# HHT_CAL-PWR_3_1.net
KiCad netlist of a schematic drawn in Altium Designer
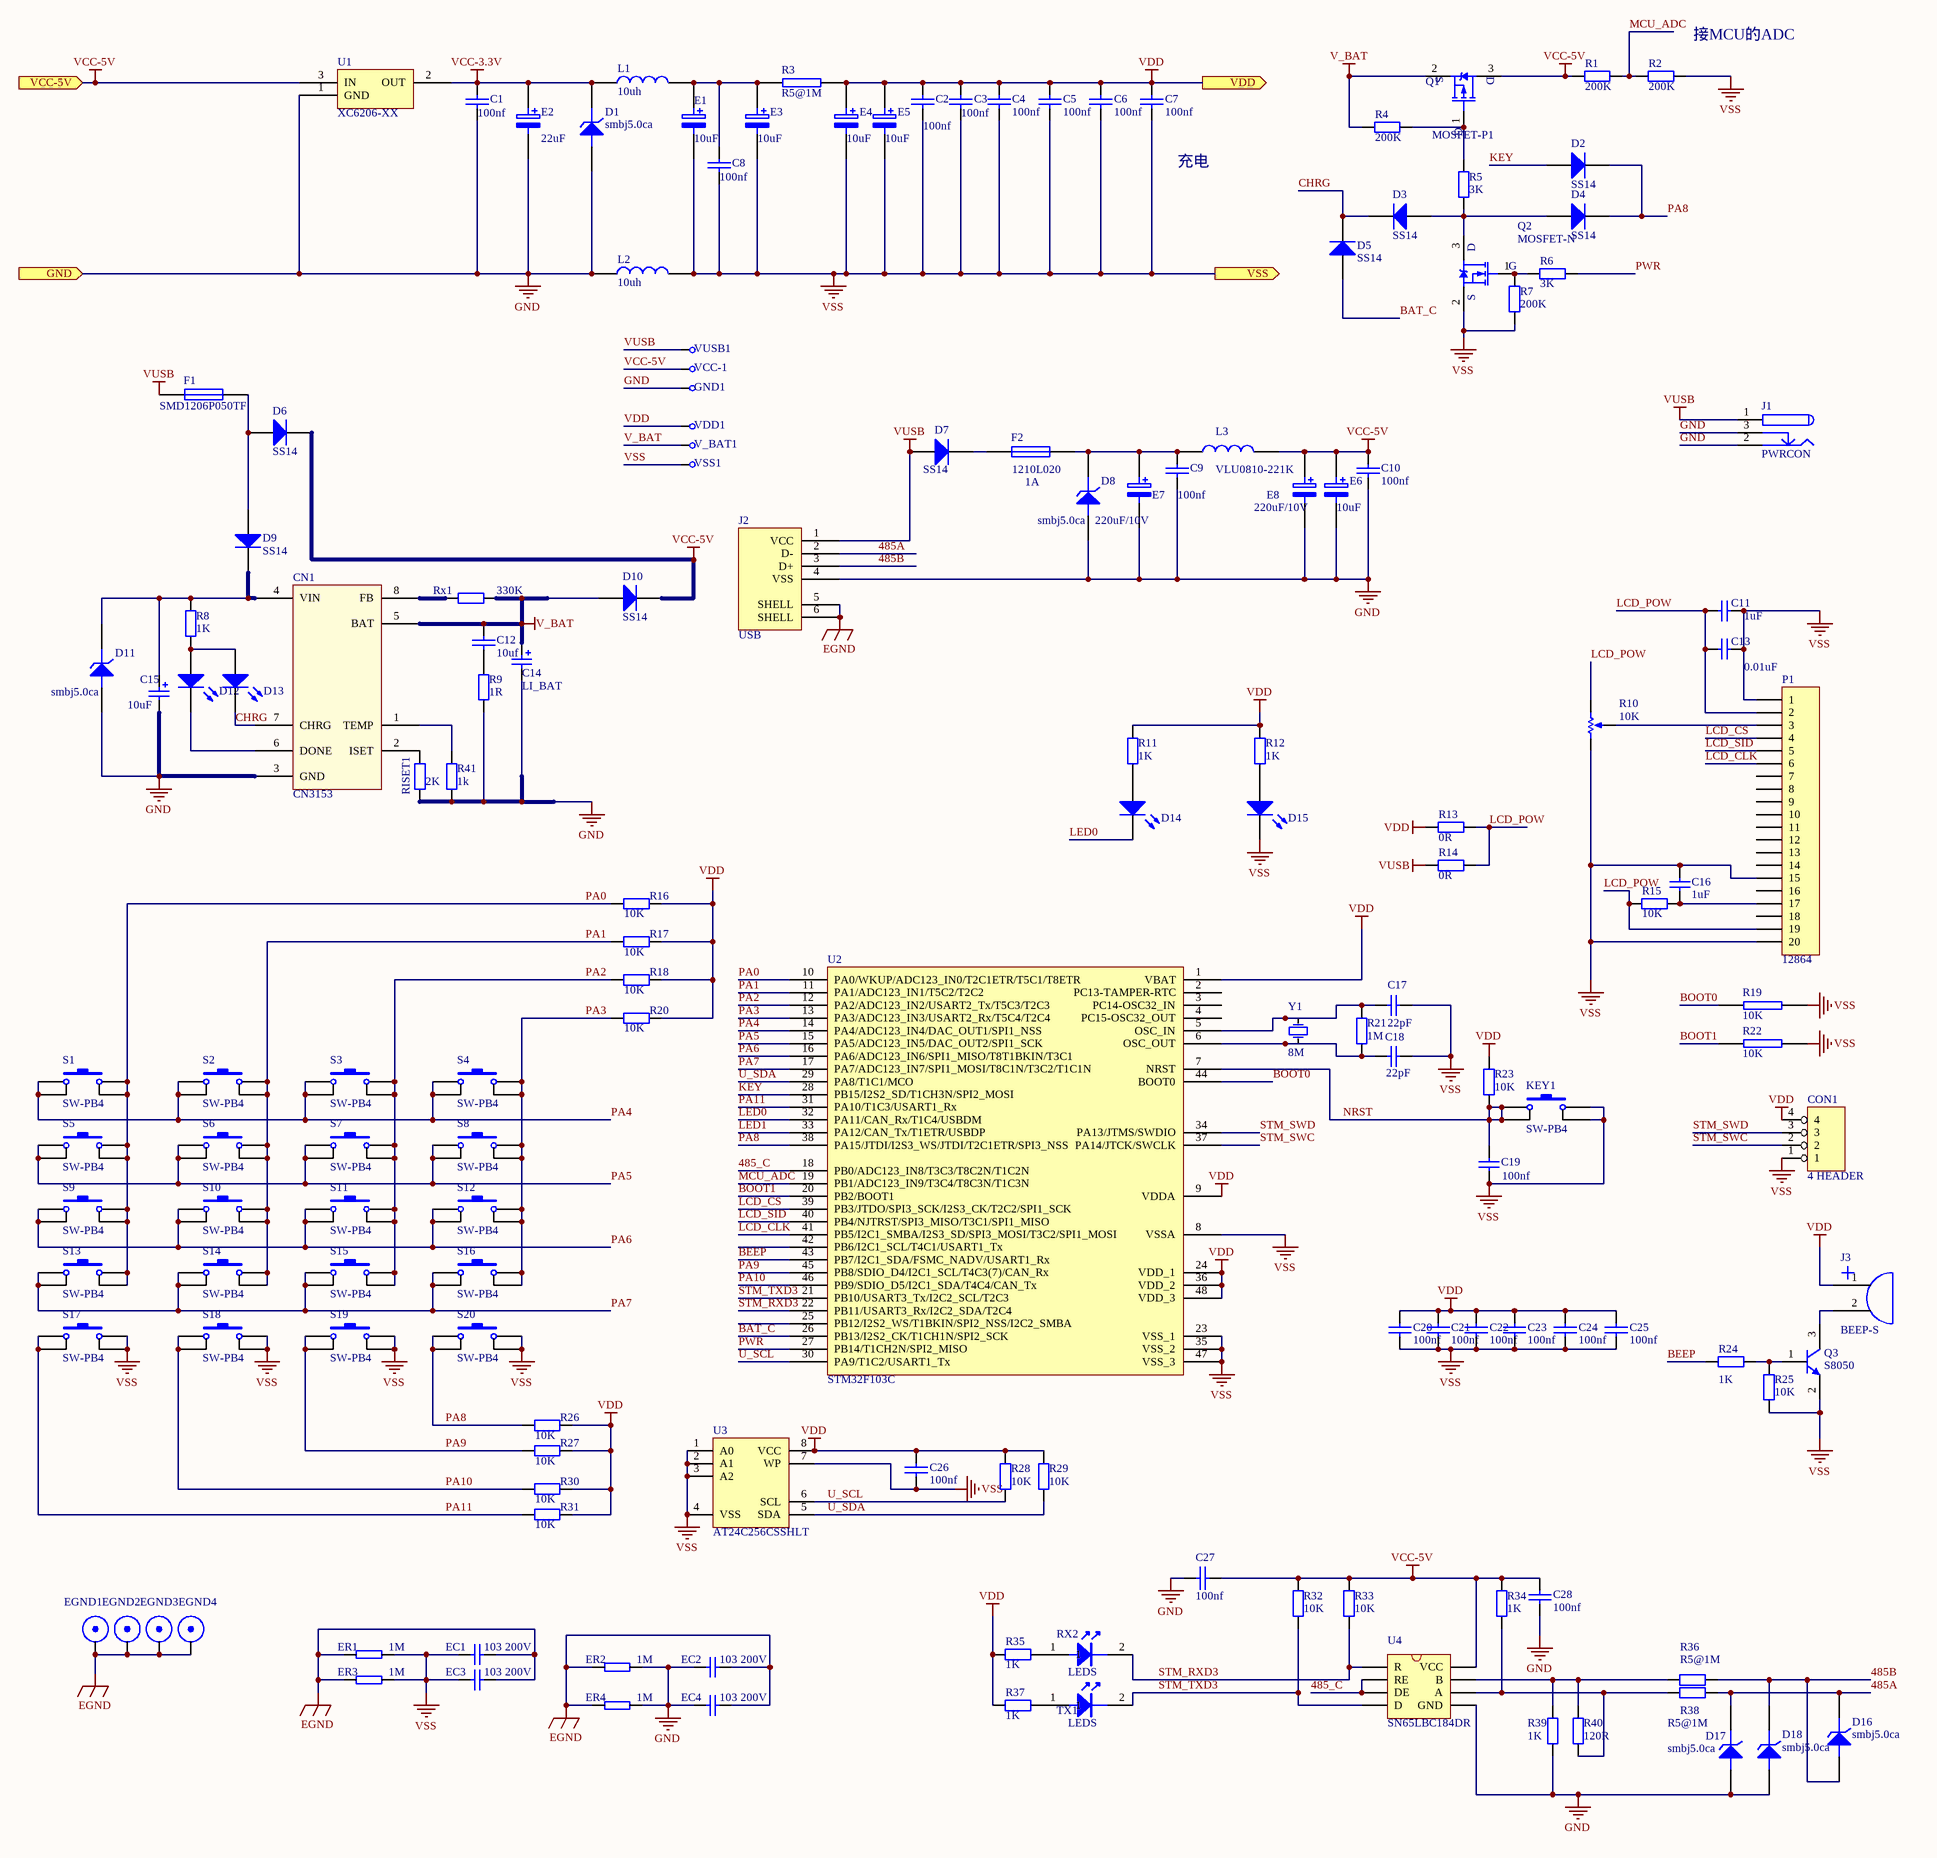
[diagram p0: HHT_CAL-PWR_3.1.SchDoc]

(export (version "E")
  (design (tool "Eeschema 10.0.6"))
  (components
    (comp (ref "C1")
      (value "100nf")
      (footprint "LC-0603_C")
      (description "Capacitor")
      (libsource (lib "Miscellaneous Devices") (part "CAP"))
    )
    (comp (ref "C2")
      (value "100nf")
      (footprint "LC-0603_C")
      (description "Capacitor")
      (libsource (lib "Miscellaneous Devices") (part "CAP"))
    )
    (comp (ref "C3")
      (value "100nf")
      (footprint "LC-0603_C")
      (description "Capacitor")
      (libsource (lib "Miscellaneous Devices") (part "CAP"))
    )
    (comp (ref "C4")
      (value "100nf")
      (footprint "LC-0603_C")
      (description "Capacitor")
      (libsource (lib "Miscellaneous Devices") (part "CAP"))
    )
    (comp (ref "C5")
      (value "100nf")
      (footprint "LC-0603_C")
      (description "Capacitor")
      (libsource (lib "Miscellaneous Devices") (part "CAP"))
    )
    (comp (ref "C6")
      (value "100nf")
      (footprint "LC-0603_C")
      (description "Capacitor")
      (libsource (lib "Miscellaneous Devices") (part "CAP"))
    )
    (comp (ref "C7")
      (value "100nf")
      (footprint "LC-0603_C")
      (description "Capacitor")
      (libsource (lib "Miscellaneous Devices") (part "CAP"))
    )
    (comp (ref "C8")
      (value "100nf")
      (footprint "LC-0603_C")
      (description "Capacitor")
      (libsource (lib "Miscellaneous Devices") (part "CAP"))
    )
    (comp (ref "C9")
      (value "100nf")
      (footprint "LC-0805_C")
      (description "Capacitor")
      (libsource (lib "Miscellaneous Devices") (part "CAP"))
    )
    (comp (ref "C10")
      (value "100nf")
      (footprint "LC-0603_C")
      (description "Capacitor")
      (libsource (lib "Miscellaneous Devices") (part "CAP"))
    )
    (comp (ref "C11")
      (value "1uF")
      (footprint "LC-0603_C")
      (description "贴片瓷片电容")
      (fields (field (name "Comment") "1uf") (field (name "PUBLISHER") "Altium Limited"))
      (libsource (lib "fszhang") (part "Cap-S"))
    )
    (comp (ref "C12")
      (value "10uf")
      (footprint "LC-CASE-A_3216")
      (description "Capacitor")
      (libsource (lib "Miscellaneous Devices") (part "CAP"))
    )
    (comp (ref "C13")
      (value "0.01uF")
      (footprint "LC-0603_C")
      (description "贴片瓷片电容")
      (fields (field (name "PUBLISHER") "Altium Limited"))
      (libsource (lib "fszhang") (part "Cap-S"))
    )
    (comp (ref "C14")
      (value "LI_BAT")
      (footprint "HDR2X1-2.54")
      (description "Polarized Capacitor (Radial)")
      (fields (field (name "PUBLISHER") "Altium Limited"))
      (libsource (lib "Miscellaneous Devices") (part "Cap Pol1"))
    )
    (comp (ref "C15")
      (value "10uF")
      (footprint "LC-CASE-B_3528")
      (description "Polarized Capacitor (Radial)")
      (fields (field (name "Comment") "100uF") (field (name "PUBLISHER") "Altium Limited"))
      (libsource (lib "Miscellaneous Devices") (part "Cap Pol1"))
    )
    (comp (ref "C16")
      (value "1uF")
      (footprint "LC-0603_C")
      (description "贴片瓷片电容")
      (fields (field (name "PUBLISHER") "Altium Limited"))
      (libsource (lib "fszhang") (part "Cap-S"))
    )
    (comp (ref "C17")
      (value "22pF")
      (footprint "LC-0603_C")
      (description "贴片瓷片电容")
      (fields (field (name "Comment") "22PF") (field (name "PUBLISHER") "Altium Limited"))
      (libsource (lib "fszhang") (part "Cap-S"))
    )
    (comp (ref "C18")
      (value "22pF")
      (footprint "LC-0603_C")
      (description "贴片瓷片电容")
      (fields (field (name "Comment") "22PF") (field (name "PUBLISHER") "Altium Limited"))
      (libsource (lib "fszhang") (part "Cap-S"))
    )
    (comp (ref "C19")
      (value "100nf")
      (footprint "LC-0603_C")
      (description "Capacitor")
      (fields (field (name "PUBLISHER") "Altium Limited"))
      (libsource (lib "Miscellaneous Devices") (part "Cap"))
    )
    (comp (ref "C20")
      (value "100nf")
      (footprint "LC-0603_C")
      (description "Capacitor")
      (libsource (lib "Miscellaneous Devices") (part "CAP"))
    )
    (comp (ref "C21")
      (value "100nf")
      (footprint "LC-0603_C")
      (description "Capacitor")
      (libsource (lib "Miscellaneous Devices") (part "CAP"))
    )
    (comp (ref "C22")
      (value "100nf")
      (footprint "LC-0603_C")
      (description "Capacitor")
      (libsource (lib "Miscellaneous Devices") (part "CAP"))
    )
    (comp (ref "C23")
      (value "100nf")
      (footprint "LC-0603_C")
      (description "Capacitor")
      (libsource (lib "Miscellaneous Devices") (part "CAP"))
    )
    (comp (ref "C24")
      (value "100nf")
      (footprint "LC-0603_C")
      (description "Capacitor")
      (libsource (lib "Miscellaneous Devices") (part "CAP"))
    )
    (comp (ref "C25")
      (value "100nf")
      (footprint "LC-0603_C")
      (description "Capacitor")
      (libsource (lib "Miscellaneous Devices") (part "CAP"))
    )
    (comp (ref "C26")
      (value "100nf")
      (footprint "LC-0603_C")
      (description "Capacitor")
      (libsource (lib "Miscellaneous Devices") (part "CAP"))
    )
    (comp (ref "C27")
      (value "100nf")
      (footprint "LC-0603_C")
      (description "Capacitor")
      (libsource (lib "Miscellaneous Devices") (part "CAP"))
    )
    (comp (ref "C28")
      (value "100nf")
      (footprint "LC-0603_C")
      (description "Capacitor")
      (libsource (lib "Miscellaneous Devices") (part "CAP"))
    )
    (comp (ref "CN1") (value "CN3153") (footprint "SOIC8") (libsource (lib "PCB_Project1") (part "CN3153")))
    (comp (ref "CON1")
      (value "4 HEADER")
      (footprint "sip4")
      (description "4 Pin Header")
      (libsource (lib "Miscellaneous Devices") (part "4 HEADER"))
    )
    (comp (ref "D1")
      (value "smbj5.0ca")
      (footprint "LC-SMB(DO-214AA)_S1")
      (description "Zener Diode")
      (libsource (lib "Miscellaneous Devices") (part "ZENER3"))
    )
    (comp (ref "D2")
      (value "SS14")
      (footprint "LC-SMA(DO-214AC)_S5")
      (description "Default Diode")
      (fields (field (name "PUBLISHER") "Altium Limited"))
      (libsource (lib "Miscellaneous Devices") (part "Diode"))
    )
    (comp (ref "D3")
      (value "SS14")
      (footprint "LC-SMA(DO-214AC)_S5")
      (description "Default Diode")
      (fields (field (name "PUBLISHER") "Altium Limited"))
      (libsource (lib "Miscellaneous Devices") (part "Diode"))
    )
    (comp (ref "D4")
      (value "SS14")
      (footprint "LC-SMA(DO-214AC)_S5")
      (description "Default Diode")
      (fields (field (name "PUBLISHER") "Altium Limited"))
      (libsource (lib "Miscellaneous Devices") (part "Diode"))
    )
    (comp (ref "D5")
      (value "SS14")
      (footprint "LC-SMA(DO-214AC)_S5")
      (description "Default Diode")
      (fields (field (name "PUBLISHER") "Altium Limited"))
      (libsource (lib "Miscellaneous Devices") (part "Diode"))
    )
    (comp (ref "D6")
      (value "SS14")
      (footprint "LC-SMA(DO-214AC)_S5")
      (description "Default Diode")
      (fields (field (name "PUBLISHER") "Altium Limited"))
      (libsource (lib "Miscellaneous Devices") (part "Diode"))
    )
    (comp (ref "D7")
      (value "SS14")
      (footprint "LC-SMA(DO-214AC)_S5")
      (description "整流二极管")
      (fields (field (name "PUBLISHER") "Altium Limited"))
      (libsource (lib "fszhang") (part "Diode-R"))
    )
    (comp (ref "D8")
      (value "smbj5.0ca")
      (footprint "LC-SMB(DO-214AA)_S1")
      (description "Zener Diode")
      (libsource (lib "Miscellaneous Devices") (part "ZENER3"))
    )
    (comp (ref "D9")
      (value "SS14")
      (footprint "LC-SMA(DO-214AC)_S5")
      (description "Default Diode")
      (fields (field (name "PUBLISHER") "Altium Limited"))
      (libsource (lib "Miscellaneous Devices") (part "Diode"))
    )
    (comp (ref "D10")
      (value "SS14")
      (footprint "LC-SMA(DO-214AC)_S5")
      (description "Default Diode")
      (fields (field (name "PUBLISHER") "Altium Limited"))
      (libsource (lib "Miscellaneous Devices") (part "Diode"))
    )
    (comp (ref "D11")
      (value "smbj5.0ca")
      (footprint "LC-SMA(DO-214AC)_S5")
      (description "Zener Diode")
      (libsource (lib "Miscellaneous Devices") (part "ZENER3"))
    )
    (comp (ref "D12")
      (value "LED0")
      (footprint "LED-0805")
      (description "发光二极管")
      (fields (field (name "PUBLISHER") "Altium Limited"))
      (libsource (lib "fszhang") (part "LED0"))
    )
    (comp (ref "D13")
      (value "LED0")
      (footprint "LED-0805")
      (description "发光二极管")
      (fields (field (name "PUBLISHER") "Altium Limited"))
      (libsource (lib "fszhang") (part "LED0"))
    )
    (comp (ref "D14")
      (value "LED0")
      (footprint "LC-0805_LED_S1")
      (description "发光二极管")
      (fields (field (name "PUBLISHER") "Altium Limited"))
      (libsource (lib "fszhang") (part "LED0"))
    )
    (comp (ref "D15")
      (value "LED0")
      (footprint "LC-0805_LED_S1")
      (description "发光二极管")
      (fields (field (name "PUBLISHER") "Altium Limited"))
      (libsource (lib "fszhang") (part "LED0"))
    )
    (comp (ref "D16")
      (value "smbj5.0ca")
      (footprint "LC-SMB(DO-214AA)_S1")
      (description "Zener Diode")
      (libsource (lib "Miscellaneous Devices") (part "ZENER3"))
    )
    (comp (ref "D17")
      (value "smbj5.0ca")
      (footprint "LC-SMB(DO-214AA)_S1")
      (description "Zener Diode")
      (libsource (lib "Miscellaneous Devices") (part "ZENER3"))
    )
    (comp (ref "D18")
      (value "smbj5.0ca")
      (footprint "LC-SMB(DO-214AA)_S1")
      (description "Zener Diode")
      (libsource (lib "Miscellaneous Devices") (part "ZENER3"))
    )
    (comp (ref "E1")
      (value "10uF")
      (footprint "LC-CASE-A_3216")
      (description "Electrolytic Capacitor")
      (libsource (lib "Miscellaneous Devices") (part "ELECTRO2"))
    )
    (comp (ref "E2")
      (value "22uF")
      (footprint "HONOR_63X54")
      (description "Electrolytic Capacitor")
      (libsource (lib "Miscellaneous Devices") (part "ELECTRO2"))
    )
    (comp (ref "E3")
      (value "10uF")
      (footprint "LC-CASE-A_3216")
      (description "Electrolytic Capacitor")
      (libsource (lib "Miscellaneous Devices") (part "ELECTRO2"))
    )
    (comp (ref "E4")
      (value "10uF")
      (footprint "LC-CASE-A_3216")
      (description "Electrolytic Capacitor")
      (libsource (lib "Miscellaneous Devices") (part "ELECTRO2"))
    )
    (comp (ref "E5")
      (value "10uF")
      (footprint "LC-CASE-A_3216")
      (description "Electrolytic Capacitor")
      (libsource (lib "Miscellaneous Devices") (part "ELECTRO2"))
    )
    (comp (ref "E6")
      (value "10uF")
      (footprint "LC-CASE-B_3528")
      (description "Electrolytic Capacitor")
      (libsource (lib "Miscellaneous Devices") (part "ELECTRO2"))
    )
    (comp (ref "E7")
      (value "220uF/10V")
      (footprint "HONOR_63X54")
      (description "Electrolytic Capacitor")
      (libsource (lib "Miscellaneous Devices") (part "ELECTRO2"))
    )
    (comp (ref "E8")
      (value "220uF/10V")
      (footprint "HONOR_63X54")
      (description "Electrolytic Capacitor")
      (libsource (lib "Miscellaneous Devices") (part "ELECTRO2"))
    )
    (comp (ref "EC1")
      (value "103 200V")
      (footprint "LC-1206_C")
      (description "Capacitor")
      (fields (field (name "PUBLISHER") "Altium Limited"))
      (libsource (lib "Miscellaneous Devices") (part "Cap"))
    )
    (comp (ref "EC2")
      (value "103 200V")
      (footprint "LC-1206_C")
      (description "Capacitor")
      (fields (field (name "PUBLISHER") "Altium Limited"))
      (libsource (lib "Miscellaneous Devices") (part "Cap"))
    )
    (comp (ref "EC3")
      (value "103 200V")
      (footprint "LC-1206_C")
      (description "Capacitor")
      (fields (field (name "PUBLISHER") "Altium Limited"))
      (libsource (lib "Miscellaneous Devices") (part "Cap"))
    )
    (comp (ref "EC4")
      (value "103 200V")
      (footprint "LC-1206_C")
      (description "Capacitor")
      (fields (field (name "PUBLISHER") "Altium Limited"))
      (libsource (lib "Miscellaneous Devices") (part "Cap"))
    )
    (comp (ref "EGND1")
      (value "EGND")
      (footprint "H-6-3.2m")
      (libsource (lib "PCB_Project_11") (part "EGND"))
    )
    (comp (ref "EGND2")
      (value "EGND")
      (footprint "H-6-3.2m")
      (libsource (lib "PCB_Project_11") (part "EGND"))
    )
    (comp (ref "EGND3")
      (value "EGND")
      (footprint "H-6-3.2m")
      (libsource (lib "PCB_Project_11") (part "EGND"))
    )
    (comp (ref "EGND4")
      (value "EGND")
      (footprint "H-6-3.2m")
      (libsource (lib "PCB_Project_11") (part "EGND"))
    )
    (comp (ref "ER1") (value "1M") (footprint "LC-1206_R") (libsource (lib "*") (part "RES2")))
    (comp (ref "ER2") (value "1M") (footprint "LC-1206_R") (libsource (lib "*") (part "RES2")))
    (comp (ref "ER3") (value "1M") (footprint "LC-1206_R") (libsource (lib "*") (part "RES2")))
    (comp (ref "ER4") (value "1M") (footprint "LC-1206_R") (libsource (lib "*") (part "RES2")))
    (comp (ref "F1")
      (value "SMD1206P050TF")
      (footprint "LC-1206_R")
      (description "Fuse")
      (fields (field (name "PUBLISHER") "Altium Limited"))
      (libsource (lib "Miscellaneous Devices") (part "Fuse 1"))
    )
    (comp (ref "F2")
      (value "1210L020")
      (footprint "LC-0805_R")
      (description "保险丝")
      (fields (field (name "ALTIUM_VALUE") "1A"))
      (libsource (lib "SCH_Footp1_Lian") (part "Fuse1"))
    )
    (comp (ref "GND1")
      (value "CHECK")
      (footprint "CHECK-B")
      (description "测试点")
      (libsource (lib "fszhang") (part "CHECK"))
    )
    (comp (ref "J1")
      (value "PWRCON")
      (footprint "DC-005")
      (description "直流电源端子")
      (fields (field (name "PUBLISHER") "Altium Limited"))
      (libsource (lib "HDR_fszhang") (part "PWRCON"))
    )
    (comp (ref "J2")
      (value "USB")
      (footprint "USB-4-A")
      (description "USB接口")
      (libsource (lib "HDR_fszhang") (part "USB"))
    )
    (comp (ref "J3")
      (value "BEEP-S")
      (footprint "BEEP-S")
      (description "有源蜂鸣器")
      (libsource (lib "fszhang") (part "BEEP-S"))
    )
    (comp (ref "KEY1")
      (value "SW-PB4")
      (footprint "金属轻触开关")
      (description "微动开关")
      (fields (field (name "PUBLISHER") "Altium Limited"))
      (libsource (lib "fszhang") (part "SW-PB4"))
    )
    (comp (ref "L1")
      (value "10uh")
      (footprint "LC-0805_L")
      (libsource (lib "Miscellaneous Devices") (part "INDUCTOR"))
    )
    (comp (ref "L2")
      (value "10uh")
      (footprint "LC-0805_L")
      (libsource (lib "Miscellaneous Devices") (part "INDUCTOR"))
    )
    (comp (ref "L3")
      (value "VLU0810-221K")
      (footprint "L-SMD-7")
      (libsource (lib "Miscellaneous Devices") (part "INDUCTOR"))
    )
    (comp (ref "P1")
      (value "12864")
      (footprint "HDR1X20")
      (description "Header, 20-Pin")
      (fields (field (name "PUBLISHER") "Altium Limited"))
      (libsource (lib "Miscellaneous Connectors") (part "Header 20"))
    )
    (comp (ref "Q1") (value "MOSFET-P1") (footprint "SOT23-3") (libsource (lib "fszhang") (part "MOSFET-P1")))
    (comp (ref "Q2")
      (value "MOSFET-N")
      (footprint "LC-SOT-23(SOT-23-3)")
      (description "N-Channel MOSFET")
      (fields (field (name "PUBLISHER") "Altium Limited"))
      (libsource (lib "fszhang") (part "MOSFET-N"))
    )
    (comp (ref "Q3")
      (value "S8050")
      (footprint "SOT23-3")
      (description "贴片三极管")
      (fields (field (name "PUBLISHER") "Altium Limited"))
      (libsource (lib "fszhang") (part "NPN1"))
    )
    (comp (ref "R1")
      (value "200K")
      (footprint "LC-0603_R")
      (description "Resistor")
      (fields (field (name "PUBLISHER") "Altium Limited"))
      (libsource (lib "Miscellaneous Devices") (part "Res2"))
    )
    (comp (ref "R2")
      (value "200K")
      (footprint "LC-0603_R")
      (description "Resistor")
      (fields (field (name "PUBLISHER") "Altium Limited"))
      (libsource (lib "Miscellaneous Devices") (part "Res2"))
    )
    (comp (ref "R3")
      (value "R5@1M")
      (footprint "LC-0805_R")
      (libsource (lib "Miscellaneous Devices") (part "RES2"))
    )
    (comp (ref "R4")
      (value "200K")
      (footprint "LC-0603_R")
      (description "Resistor")
      (fields (field (name "PUBLISHER") "Altium Limited"))
      (libsource (lib "Miscellaneous Devices") (part "Res2"))
    )
    (comp (ref "R5")
      (value "3K")
      (footprint "LC-0603_R")
      (description "Resistor")
      (fields (field (name "PUBLISHER") "Altium Limited"))
      (libsource (lib "") (part "Res2_1"))
    )
    (comp (ref "R6")
      (value "3K")
      (footprint "LC-0603_R")
      (description "Resistor")
      (fields (field (name "PUBLISHER") "Altium Limited"))
      (libsource (lib "") (part "Res2_3"))
    )
    (comp (ref "R7")
      (value "200K")
      (footprint "LC-0603_R")
      (description "Resistor")
      (fields (field (name "PUBLISHER") "Altium Limited"))
      (libsource (lib "") (part "Res2_1"))
    )
    (comp (ref "R8")
      (value "1K")
      (footprint "LC-0603_R")
      (description "Resistor")
      (fields (field (name "PUBLISHER") "Altium Limited"))
      (libsource (lib "") (part "Res2_1"))
    )
    (comp (ref "R9")
      (value "1R")
      (footprint "LC-0603_R")
      (description "Resistor")
      (fields (field (name "PUBLISHER") "Altium Limited"))
      (libsource (lib "") (part "Res2_2"))
    )
    (comp (ref "R10")
      (value "10K")
      (footprint "VR-3296W")
      (description "精密可调电阻")
      (fields (field (name "Comment") "RPot") (field (name "PUBLISHER") "Altium Limited"))
      (libsource (lib "fszhang") (part "RPot"))
    )
    (comp (ref "R11")
      (value "1K")
      (footprint "0805-1")
      (description "贴片电阻")
      (fields (field (name "PUBLISHER") "Altium Limited"))
      (libsource (lib "fszhang") (part "Res1"))
    )
    (comp (ref "R12")
      (value "1K")
      (footprint "0805-1")
      (description "贴片电阻")
      (fields (field (name "PUBLISHER") "Altium Limited"))
      (libsource (lib "fszhang") (part "Res1"))
    )
    (comp (ref "R13")
      (value "0R")
      (footprint "LC-0805_R")
      (description "贴片电阻")
      (fields (field (name "PUBLISHER") "Altium Limited"))
      (libsource (lib "") (part "Res1_1"))
    )
    (comp (ref "R14")
      (value "0R")
      (footprint "LC-0805_R")
      (description "贴片电阻")
      (fields (field (name "PUBLISHER") "Altium Limited"))
      (libsource (lib "") (part "Res1_1"))
    )
    (comp (ref "R15")
      (value "10K")
      (footprint "0805-1")
      (description "贴片电阻")
      (fields (field (name "PUBLISHER") "Altium Limited"))
      (libsource (lib "") (part "Res1_1"))
    )
    (comp (ref "R16")
      (value "10K")
      (footprint "LC-0603_R")
      (description "贴片电阻")
      (fields (field (name "PUBLISHER") "Altium Limited"))
      (libsource (lib "") (part "Res1_1"))
    )
    (comp (ref "R17")
      (value "10K")
      (footprint "LC-0603_R")
      (description "贴片电阻")
      (fields (field (name "PUBLISHER") "Altium Limited"))
      (libsource (lib "") (part "Res1_1"))
    )
    (comp (ref "R18")
      (value "10K")
      (footprint "LC-0603_R")
      (description "贴片电阻")
      (fields (field (name "PUBLISHER") "Altium Limited"))
      (libsource (lib "") (part "Res1_1"))
    )
    (comp (ref "R19")
      (value "10K")
      (footprint "LC-0603_R")
      (libsource (lib "Miscellaneous Devices") (part "RES2"))
    )
    (comp (ref "R20")
      (value "10K")
      (footprint "LC-0603_R")
      (description "贴片电阻")
      (fields (field (name "PUBLISHER") "Altium Limited"))
      (libsource (lib "") (part "Res1_1"))
    )
    (comp (ref "R21")
      (value "1M")
      (footprint "0603-1")
      (description "贴片电阻")
      (fields (field (name "PUBLISHER") "Altium Limited"))
      (libsource (lib "fszhang") (part "Res1"))
    )
    (comp (ref "R22")
      (value "10K")
      (footprint "LC-0603_R")
      (libsource (lib "Miscellaneous Devices") (part "RES2"))
    )
    (comp (ref "R23")
      (value "10K")
      (footprint "LC-0603_R")
      (description "Resistor")
      (fields (field (name "PUBLISHER") "Altium Limited"))
      (libsource (lib "") (part "Res2_1"))
    )
    (comp (ref "R24")
      (value "1K")
      (footprint "LC-0603_R")
      (description "贴片电阻")
      (fields (field (name "PUBLISHER") "Altium Limited"))
      (libsource (lib "") (part "Res1_1"))
    )
    (comp (ref "R25")
      (value "10K")
      (footprint "LC-0603_R")
      (description "贴片电阻")
      (fields (field (name "Comment") "10k") (field (name "PUBLISHER") "Altium Limited"))
      (libsource (lib "fszhang") (part "Res1"))
    )
    (comp (ref "R26")
      (value "10K")
      (footprint "LC-0603_R")
      (description "贴片电阻")
      (fields (field (name "PUBLISHER") "Altium Limited"))
      (libsource (lib "") (part "Res1_1"))
    )
    (comp (ref "R27")
      (value "10K")
      (footprint "LC-0603_R")
      (description "贴片电阻")
      (fields (field (name "PUBLISHER") "Altium Limited"))
      (libsource (lib "") (part "Res1_1"))
    )
    (comp (ref "R28")
      (value "10K")
      (footprint "LC-0603_R")
      (description "Resistor")
      (fields (field (name "PUBLISHER") "Altium Limited"))
      (libsource (lib "") (part "Res2_2"))
    )
    (comp (ref "R29")
      (value "10K")
      (footprint "LC-0603_R")
      (description "Resistor")
      (fields (field (name "PUBLISHER") "Altium Limited"))
      (libsource (lib "") (part "Res2_2"))
    )
    (comp (ref "R30")
      (value "10K")
      (footprint "LC-0603_R")
      (description "贴片电阻")
      (fields (field (name "PUBLISHER") "Altium Limited"))
      (libsource (lib "") (part "Res1_1"))
    )
    (comp (ref "R31")
      (value "10K")
      (footprint "LC-0603_R")
      (description "贴片电阻")
      (fields (field (name "PUBLISHER") "Altium Limited"))
      (libsource (lib "") (part "Res1_1"))
    )
    (comp (ref "R32")
      (value "10K")
      (footprint "LC-0603_r")
      (description "Resistor")
      (fields (field (name "PUBLISHER") "Altium Limited"))
      (libsource (lib "") (part "Res2_1"))
    )
    (comp (ref "R33")
      (value "10K")
      (footprint "LC-0603_r")
      (description "Resistor")
      (fields (field (name "PUBLISHER") "Altium Limited"))
      (libsource (lib "") (part "Res2_1"))
    )
    (comp (ref "R34")
      (value "1K")
      (footprint "LC-0603_R")
      (description "Resistor")
      (fields (field (name "PUBLISHER") "Altium Limited"))
      (libsource (lib "") (part "Res2_1"))
    )
    (comp (ref "R35")
      (value "1K")
      (footprint "LC-0603_R")
      (description "Resistor")
      (fields (field (name "PUBLISHER") "Altium Limited"))
      (libsource (lib "Miscellaneous Devices") (part "Res2"))
    )
    (comp (ref "R36")
      (value "R5@1M")
      (footprint "LC-0805_R")
      (description "Resistor")
      (fields (field (name "PUBLISHER") "Altium Limited"))
      (libsource (lib "") (part "Res2_3"))
    )
    (comp (ref "R37")
      (value "1K")
      (footprint "LC-0603_R")
      (description "Resistor")
      (fields (field (name "PUBLISHER") "Altium Limited"))
      (libsource (lib "Miscellaneous Devices") (part "Res2"))
    )
    (comp (ref "R38")
      (value "R5@1M")
      (footprint "LC-0805_R")
      (description "Resistor")
      (fields (field (name "PUBLISHER") "Altium Limited"))
      (libsource (lib "") (part "Res2_3"))
    )
    (comp (ref "R39")
      (value "1K")
      (footprint "LC-0603_R")
      (description "Resistor")
      (fields (field (name "PUBLISHER") "Altium Limited"))
      (libsource (lib "") (part "Res2_1"))
    )
    (comp (ref "R40")
      (value "120R")
      (footprint "LC-0603_R")
      (description "Resistor")
      (fields (field (name "PUBLISHER") "Altium Limited"))
      (libsource (lib "") (part "Res2_1"))
    )
    (comp (ref "R41")
      (value "1k")
      (footprint "LC-0603_R")
      (description "Resistor")
      (fields (field (name "PUBLISHER") "Altium Limited"))
      (libsource (lib "") (part "Res2_2"))
    )
    (comp (ref "RISET1")
      (value "2K")
      (footprint "LC-0603_R")
      (description "Resistor")
      (fields (field (name "PUBLISHER") "Altium Limited"))
      (libsource (lib "") (part "Res2_2"))
    )
    (comp (ref "Rx1")
      (value "330K")
      (footprint "LC-0603_R")
      (description "Resistor")
      (fields (field (name "PUBLISHER") "Altium Limited"))
      (libsource (lib "") (part "Res2_3"))
    )
    (comp (ref "RX2")
      (value "LEDS")
      (footprint "LC-0805_LED_S1")
      (libsource (lib "SCH_Footp1_Lian") (part "LEDS"))
    )
    (comp (ref "S1")
      (value "SW-PB4")
      (footprint "金属轻触开关")
      (description "微动开关")
      (fields (field (name "PUBLISHER") "Altium Limited"))
      (libsource (lib "fszhang") (part "SW-PB4"))
    )
    (comp (ref "S2")
      (value "SW-PB4")
      (footprint "金属轻触开关")
      (description "微动开关")
      (fields (field (name "PUBLISHER") "Altium Limited"))
      (libsource (lib "fszhang") (part "SW-PB4"))
    )
    (comp (ref "S3")
      (value "SW-PB4")
      (footprint "金属轻触开关")
      (description "微动开关")
      (fields (field (name "PUBLISHER") "Altium Limited"))
      (libsource (lib "fszhang") (part "SW-PB4"))
    )
    (comp (ref "S4")
      (value "SW-PB4")
      (footprint "金属轻触开关")
      (description "微动开关")
      (fields (field (name "PUBLISHER") "Altium Limited"))
      (libsource (lib "fszhang") (part "SW-PB4"))
    )
    (comp (ref "S5")
      (value "SW-PB4")
      (footprint "金属轻触开关")
      (description "微动开关")
      (fields (field (name "PUBLISHER") "Altium Limited"))
      (libsource (lib "fszhang") (part "SW-PB4"))
    )
    (comp (ref "S6")
      (value "SW-PB4")
      (footprint "金属轻触开关")
      (description "微动开关")
      (fields (field (name "PUBLISHER") "Altium Limited"))
      (libsource (lib "fszhang") (part "SW-PB4"))
    )
    (comp (ref "S7")
      (value "SW-PB4")
      (footprint "金属轻触开关")
      (description "微动开关")
      (fields (field (name "PUBLISHER") "Altium Limited"))
      (libsource (lib "fszhang") (part "SW-PB4"))
    )
    (comp (ref "S8")
      (value "SW-PB4")
      (footprint "金属轻触开关")
      (description "微动开关")
      (fields (field (name "PUBLISHER") "Altium Limited"))
      (libsource (lib "fszhang") (part "SW-PB4"))
    )
    (comp (ref "S9")
      (value "SW-PB4")
      (footprint "金属轻触开关")
      (description "微动开关")
      (fields (field (name "PUBLISHER") "Altium Limited"))
      (libsource (lib "fszhang") (part "SW-PB4"))
    )
    (comp (ref "S10")
      (value "SW-PB4")
      (footprint "金属轻触开关")
      (description "微动开关")
      (fields (field (name "PUBLISHER") "Altium Limited"))
      (libsource (lib "fszhang") (part "SW-PB4"))
    )
    (comp (ref "S11")
      (value "SW-PB4")
      (footprint "金属轻触开关")
      (description "微动开关")
      (fields (field (name "PUBLISHER") "Altium Limited"))
      (libsource (lib "fszhang") (part "SW-PB4"))
    )
    (comp (ref "S12")
      (value "SW-PB4")
      (footprint "金属轻触开关")
      (description "微动开关")
      (fields (field (name "PUBLISHER") "Altium Limited"))
      (libsource (lib "fszhang") (part "SW-PB4"))
    )
    (comp (ref "S13")
      (value "SW-PB4")
      (footprint "金属轻触开关")
      (description "微动开关")
      (fields (field (name "PUBLISHER") "Altium Limited"))
      (libsource (lib "fszhang") (part "SW-PB4"))
    )
    (comp (ref "S14")
      (value "SW-PB4")
      (footprint "金属轻触开关")
      (description "微动开关")
      (fields (field (name "PUBLISHER") "Altium Limited"))
      (libsource (lib "fszhang") (part "SW-PB4"))
    )
    (comp (ref "S15")
      (value "SW-PB4")
      (footprint "金属轻触开关")
      (description "微动开关")
      (fields (field (name "PUBLISHER") "Altium Limited"))
      (libsource (lib "fszhang") (part "SW-PB4"))
    )
    (comp (ref "S16")
      (value "SW-PB4")
      (footprint "金属轻触开关")
      (description "微动开关")
      (fields (field (name "PUBLISHER") "Altium Limited"))
      (libsource (lib "fszhang") (part "SW-PB4"))
    )
    (comp (ref "S17")
      (value "SW-PB4")
      (footprint "金属轻触开关")
      (description "微动开关")
      (fields (field (name "PUBLISHER") "Altium Limited"))
      (libsource (lib "fszhang") (part "SW-PB4"))
    )
    (comp (ref "S18")
      (value "SW-PB4")
      (footprint "金属轻触开关")
      (description "微动开关")
      (fields (field (name "PUBLISHER") "Altium Limited"))
      (libsource (lib "fszhang") (part "SW-PB4"))
    )
    (comp (ref "S19")
      (value "SW-PB4")
      (footprint "金属轻触开关")
      (description "微动开关")
      (fields (field (name "PUBLISHER") "Altium Limited"))
      (libsource (lib "fszhang") (part "SW-PB4"))
    )
    (comp (ref "S20")
      (value "SW-PB4")
      (footprint "金属轻触开关")
      (description "微动开关")
      (fields (field (name "PUBLISHER") "Altium Limited"))
      (libsource (lib "fszhang") (part "SW-PB4"))
    )
    (comp (ref "TX1")
      (value "LEDS")
      (footprint "LC-0805_LED_S1")
      (libsource (lib "SCH_Footp1_Lian") (part "LEDS"))
    )
    (comp (ref "U1")
      (value "XC6206-XX")
      (footprint "LC-SOT-23(SOT-23-3)")
      (libsource (lib "fszhang") (part "XC6206-XX"))
    )
    (comp (ref "U2")
      (value "STM32F103C")
      (footprint "LC-LQFP-48_7x7x05P")
      (description "STM32单片机48引脚")
      (libsource (lib "fszhang") (part "STM32F103C"))
    )
    (comp (ref "U3")
      (value "AT24C256CSSHLT")
      (footprint "SOIC-8")
      (description "EEROM存储器")
      (libsource (lib "SCH_Footp1_Lian") (part "AT24C02"))
    )
    (comp (ref "U4") (value "SN65LBC184DR") (footprint "soic-8") (libsource (lib "*") (part "75176B")))
    (comp (ref "VCC-1")
      (value "CHECK")
      (footprint "CHECK-B")
      (description "测试点")
      (libsource (lib "fszhang") (part "CHECK"))
    )
    (comp (ref "VDD1")
      (value "CHECK")
      (footprint "CHECK-B")
      (description "测试点")
      (libsource (lib "fszhang") (part "CHECK"))
    )
    (comp (ref "VSS1")
      (value "CHECK")
      (footprint "CHECK-B")
      (description "测试点")
      (libsource (lib "fszhang") (part "CHECK"))
    )
    (comp (ref "VUSB1")
      (value "CHECK")
      (footprint "CHECK-B")
      (description "测试点")
      (libsource (lib "fszhang") (part "CHECK"))
    )
    (comp (ref "V_BAT1")
      (value "CHECK")
      (footprint "CHECK-B")
      (description "测试点")
      (libsource (lib "fszhang") (part "CHECK"))
    )
    (comp (ref "Y1")
      (value "8M")
      (footprint "X-SM49")
      (description "晶振")
      (fields (field (name "Comment") "XTAL") (field (name "PUBLISHER") "Altium Limited"))
      (libsource (lib "fszhang") (part "XTAL"))
    )
  )
  (nets
    (net (code "1") (name "/485A") (class "Default")
      (node (ref "D16") (pin "2") (pinfunction "K_2") (pintype "passive"))
      (node (ref "D17") (pin "2") (pinfunction "K_2") (pintype "passive"))
      (node (ref "J2") (pin "2") (pinfunction "D-_2") (pintype "passive"))
      (node (ref "R38") (pin "1") (pinfunction "1_1") (pintype "passive"))
    )
    (net (code "2") (name "/485B") (class "Default")
      (node (ref "D16") (pin "1") (pinfunction "A_1") (pintype "passive"))
      (node (ref "D18") (pin "2") (pinfunction "K_2") (pintype "passive"))
      (node (ref "J2") (pin "3") (pinfunction "D+_3") (pintype "passive"))
      (node (ref "R36") (pin "1") (pinfunction "1_1") (pintype "passive"))
    )
    (net (code "3") (name "/485_C") (class "Default")
      (node (ref "U2") (pin "18") (pinfunction "PB0/ADC123_IN8/T3C3/T8C2N/T1C2N_18") (pintype "passive"))
      (node (ref "U4") (pin "2") (pinfunction "RE_2") (pintype "passive"))
      (node (ref "U4") (pin "3") (pinfunction "DE_3") (pintype "passive"))
    )
    (net (code "4") (name "/BAT_C") (class "Default")
      (node (ref "D5") (pin "1") (pinfunction "A_1") (pintype "passive"))
      (node (ref "U2") (pin "26") (pinfunction "PB13/I2S2_CK/T1CH1N/SPI2_SCK_26") (pintype "passive"))
    )
    (net (code "5") (name "/BEEP") (class "Default")
      (node (ref "R24") (pin "1") (pinfunction "1_1") (pintype "passive"))
      (node (ref "U2") (pin "43") (pinfunction "PB7/I2C1_SDA/FSMC_NADV/USART1_Rx_43") (pintype "passive"))
    )
    (net (code "6") (name "/BOOT0") (class "Default")
      (node (ref "R19") (pin "2") (pinfunction "2_2") (pintype "passive"))
      (node (ref "U2") (pin "44") (pinfunction "BOOT0_44") (pintype "passive"))
    )
    (net (code "7") (name "/BOOT1") (class "Default")
      (node (ref "R22") (pin "2") (pinfunction "2_2") (pintype "passive"))
      (node (ref "U2") (pin "20") (pinfunction "PB2/BOOT1_20") (pintype "passive"))
    )
    (net (code "8") (name "/CHRG") (class "Default")
      (node (ref "CN1") (pin "7") (pinfunction "CHRG_7") (pintype "passive"))
      (node (ref "D13") (pin "2") (pinfunction "K_2") (pintype "passive"))
      (node (ref "D3") (pin "2") (pinfunction "K_2") (pintype "passive"))
      (node (ref "D5") (pin "2") (pinfunction "K_2") (pintype "passive"))
    )
    (net (code "9") (name "/KEY") (class "Default")
      (node (ref "D2") (pin "1") (pinfunction "A_1") (pintype "passive"))
      (node (ref "U2") (pin "28") (pinfunction "PB15/I2S2_SD/T1CH3N/SPI2_MOSI_28") (pintype "passive"))
    )
    (net (code "10") (name "/LCD_CLK") (class "Default")
      (node (ref "P1") (pin "6") (pinfunction "6_6") (pintype "passive"))
      (node (ref "U2") (pin "41") (pinfunction "PB5/I2C1_SMBA/I2S3_SD/SPI3_MOSI/T3C2/SPI1_MOSI_41") (pintype "passive"))
    )
    (net (code "11") (name "/LCD_CS") (class "Default")
      (node (ref "P1") (pin "4") (pinfunction "4_4") (pintype "passive"))
      (node (ref "U2") (pin "39") (pinfunction "PB3/JTDO/SPI3_SCK/I2S3_CK/T2C2/SPI1_SCK_39") (pintype "passive"))
    )
    (net (code "12") (name "/LCD_POW") (class "Default")
      (node (ref "C11") (pin "1") (pinfunction "1_1") (pintype "passive"))
      (node (ref "C13") (pin "1") (pinfunction "1_1") (pintype "passive"))
      (node (ref "P1") (pin "19") (pinfunction "19_19") (pintype "passive"))
      (node (ref "P1") (pin "2") (pinfunction "2_2") (pintype "passive"))
      (node (ref "R10") (pin "3") (pinfunction "BOT_3") (pintype "passive"))
      (node (ref "R13") (pin "2") (pinfunction "2_2") (pintype "passive"))
      (node (ref "R14") (pin "2") (pinfunction "2_2") (pintype "passive"))
      (node (ref "R15") (pin "1") (pinfunction "1_1") (pintype "passive"))
    )
    (net (code "13") (name "/LCD_SID") (class "Default")
      (node (ref "P1") (pin "5") (pinfunction "5_5") (pintype "passive"))
      (node (ref "U2") (pin "40") (pinfunction "PB4/NJTRST/SPI3_MISO/T3C1/SPI1_MISO_40") (pintype "passive"))
    )
    (net (code "14") (name "/LED0") (class "Default")
      (node (ref "D14") (pin "2") (pinfunction "K_2") (pintype "passive"))
      (node (ref "U2") (pin "32") (pinfunction "PA11/CAN_Rx/T1C4/USBDM_32") (pintype "passive"))
    )
    (net (code "15") (name "/LED1") (class "Default")
      (node (ref "U2") (pin "33") (pinfunction "PA12/CAN_Tx/T1ETR/USBDP_33") (pintype "passive"))
    )
    (net (code "16") (name "/MCU_ADC") (class "Default")
      (node (ref "R1") (pin "2") (pinfunction "2_2") (pintype "passive"))
      (node (ref "R2") (pin "1") (pinfunction "1_1") (pintype "passive"))
      (node (ref "U2") (pin "19") (pinfunction "PB1/ADC123_IN9/T3C4/T8C3N/T1C3N_19") (pintype "passive"))
    )
    (net (code "17") (name "/NRST") (class "Default")
      (node (ref "C19") (pin "2") (pinfunction "2_2") (pintype "passive"))
      (node (ref "KEY1") (pin "1") (pinfunction "1_1") (pintype "passive"))
      (node (ref "KEY1") (pin "4") (pinfunction "4_4") (pintype "passive"))
      (node (ref "R23") (pin "1") (pinfunction "1_1") (pintype "passive"))
      (node (ref "U2") (pin "7") (pinfunction "NRST_7") (pintype "passive"))
    )
    (net (code "18") (name "/PA0") (class "Default")
      (node (ref "R16") (pin "1") (pinfunction "1_1") (pintype "passive"))
      (node (ref "S1") (pin "2") (pinfunction "2_2") (pintype "passive"))
      (node (ref "S1") (pin "3") (pinfunction "3_3") (pintype "passive"))
      (node (ref "S13") (pin "2") (pinfunction "2_2") (pintype "passive"))
      (node (ref "S13") (pin "3") (pinfunction "3_3") (pintype "passive"))
      (node (ref "S5") (pin "2") (pinfunction "2_2") (pintype "passive"))
      (node (ref "S5") (pin "3") (pinfunction "3_3") (pintype "passive"))
      (node (ref "S9") (pin "2") (pinfunction "2_2") (pintype "passive"))
      (node (ref "S9") (pin "3") (pinfunction "3_3") (pintype "passive"))
      (node (ref "U2") (pin "10") (pinfunction "PA0/WKUP/ADC123_IN0/T2C1ETR/T5C1/T8ETR_10") (pintype "passive"))
    )
    (net (code "19") (name "/PA1") (class "Default")
      (node (ref "R17") (pin "1") (pinfunction "1_1") (pintype "passive"))
      (node (ref "S10") (pin "2") (pinfunction "2_2") (pintype "passive"))
      (node (ref "S10") (pin "3") (pinfunction "3_3") (pintype "passive"))
      (node (ref "S14") (pin "2") (pinfunction "2_2") (pintype "passive"))
      (node (ref "S14") (pin "3") (pinfunction "3_3") (pintype "passive"))
      (node (ref "S2") (pin "2") (pinfunction "2_2") (pintype "passive"))
      (node (ref "S2") (pin "3") (pinfunction "3_3") (pintype "passive"))
      (node (ref "S6") (pin "2") (pinfunction "2_2") (pintype "passive"))
      (node (ref "S6") (pin "3") (pinfunction "3_3") (pintype "passive"))
      (node (ref "U2") (pin "11") (pinfunction "PA1/ADC123_IN1/T5C2/T2C2_11") (pintype "passive"))
    )
    (net (code "20") (name "/PA2") (class "Default")
      (node (ref "R18") (pin "1") (pinfunction "1_1") (pintype "passive"))
      (node (ref "S11") (pin "2") (pinfunction "2_2") (pintype "passive"))
      (node (ref "S11") (pin "3") (pinfunction "3_3") (pintype "passive"))
      (node (ref "S15") (pin "2") (pinfunction "2_2") (pintype "passive"))
      (node (ref "S15") (pin "3") (pinfunction "3_3") (pintype "passive"))
      (node (ref "S3") (pin "2") (pinfunction "2_2") (pintype "passive"))
      (node (ref "S3") (pin "3") (pinfunction "3_3") (pintype "passive"))
      (node (ref "S7") (pin "2") (pinfunction "2_2") (pintype "passive"))
      (node (ref "S7") (pin "3") (pinfunction "3_3") (pintype "passive"))
      (node (ref "U2") (pin "12") (pinfunction "PA2/ADC123_IN2/USART2_Tx/T5C3/T2C3_12") (pintype "passive"))
    )
    (net (code "21") (name "/PA3") (class "Default")
      (node (ref "R20") (pin "1") (pinfunction "1_1") (pintype "passive"))
      (node (ref "S12") (pin "2") (pinfunction "2_2") (pintype "passive"))
      (node (ref "S12") (pin "3") (pinfunction "3_3") (pintype "passive"))
      (node (ref "S16") (pin "2") (pinfunction "2_2") (pintype "passive"))
      (node (ref "S16") (pin "3") (pinfunction "3_3") (pintype "passive"))
      (node (ref "S4") (pin "2") (pinfunction "2_2") (pintype "passive"))
      (node (ref "S4") (pin "3") (pinfunction "3_3") (pintype "passive"))
      (node (ref "S8") (pin "2") (pinfunction "2_2") (pintype "passive"))
      (node (ref "S8") (pin "3") (pinfunction "3_3") (pintype "passive"))
      (node (ref "U2") (pin "13") (pinfunction "PA3/ADC123_IN3/USART2_Rx/T5C4/T2C4_13") (pintype "passive"))
    )
    (net (code "22") (name "/PA4") (class "Default")
      (node (ref "S1") (pin "1") (pinfunction "1_1") (pintype "passive"))
      (node (ref "S1") (pin "4") (pinfunction "4_4") (pintype "passive"))
      (node (ref "S2") (pin "1") (pinfunction "1_1") (pintype "passive"))
      (node (ref "S2") (pin "4") (pinfunction "4_4") (pintype "passive"))
      (node (ref "S3") (pin "1") (pinfunction "1_1") (pintype "passive"))
      (node (ref "S3") (pin "4") (pinfunction "4_4") (pintype "passive"))
      (node (ref "S4") (pin "1") (pinfunction "1_1") (pintype "passive"))
      (node (ref "S4") (pin "4") (pinfunction "4_4") (pintype "passive"))
      (node (ref "U2") (pin "14") (pinfunction "PA4/ADC123_IN4/DAC_OUT1/SPI1_NSS_14") (pintype "passive"))
    )
    (net (code "23") (name "/PA5") (class "Default")
      (node (ref "S5") (pin "1") (pinfunction "1_1") (pintype "passive"))
      (node (ref "S5") (pin "4") (pinfunction "4_4") (pintype "passive"))
      (node (ref "S6") (pin "1") (pinfunction "1_1") (pintype "passive"))
      (node (ref "S6") (pin "4") (pinfunction "4_4") (pintype "passive"))
      (node (ref "S7") (pin "1") (pinfunction "1_1") (pintype "passive"))
      (node (ref "S7") (pin "4") (pinfunction "4_4") (pintype "passive"))
      (node (ref "S8") (pin "1") (pinfunction "1_1") (pintype "passive"))
      (node (ref "S8") (pin "4") (pinfunction "4_4") (pintype "passive"))
      (node (ref "U2") (pin "15") (pinfunction "PA5/ADC123_IN5/DAC_OUT2/SPI1_SCK_15") (pintype "passive"))
    )
    (net (code "24") (name "/PA6") (class "Default")
      (node (ref "S10") (pin "1") (pinfunction "1_1") (pintype "passive"))
      (node (ref "S10") (pin "4") (pinfunction "4_4") (pintype "passive"))
      (node (ref "S11") (pin "1") (pinfunction "1_1") (pintype "passive"))
      (node (ref "S11") (pin "4") (pinfunction "4_4") (pintype "passive"))
      (node (ref "S12") (pin "1") (pinfunction "1_1") (pintype "passive"))
      (node (ref "S12") (pin "4") (pinfunction "4_4") (pintype "passive"))
      (node (ref "S9") (pin "1") (pinfunction "1_1") (pintype "passive"))
      (node (ref "S9") (pin "4") (pinfunction "4_4") (pintype "passive"))
      (node (ref "U2") (pin "16") (pinfunction "PA6/ADC123_IN6/SPI1_MISO/T8T1BKIN/T3C1_16") (pintype "passive"))
    )
    (net (code "25") (name "/PA7") (class "Default")
      (node (ref "S13") (pin "1") (pinfunction "1_1") (pintype "passive"))
      (node (ref "S13") (pin "4") (pinfunction "4_4") (pintype "passive"))
      (node (ref "S14") (pin "1") (pinfunction "1_1") (pintype "passive"))
      (node (ref "S14") (pin "4") (pinfunction "4_4") (pintype "passive"))
      (node (ref "S15") (pin "1") (pinfunction "1_1") (pintype "passive"))
      (node (ref "S15") (pin "4") (pinfunction "4_4") (pintype "passive"))
      (node (ref "S16") (pin "1") (pinfunction "1_1") (pintype "passive"))
      (node (ref "S16") (pin "4") (pinfunction "4_4") (pintype "passive"))
      (node (ref "U2") (pin "17") (pinfunction "PA7/ADC123_IN7/SPI1_MOSI/T8C1N/T3C2/T1C1N_17") (pintype "passive"))
    )
    (net (code "26") (name "/PA8") (class "Default")
      (node (ref "D2") (pin "2") (pinfunction "K_2") (pintype "passive"))
      (node (ref "D4") (pin "2") (pinfunction "K_2") (pintype "passive"))
      (node (ref "R26") (pin "1") (pinfunction "1_1") (pintype "passive"))
      (node (ref "S20") (pin "1") (pinfunction "1_1") (pintype "passive"))
      (node (ref "S20") (pin "4") (pinfunction "4_4") (pintype "passive"))
      (node (ref "U2") (pin "38") (pinfunction "PA15/JTDI/I2S3_WS/JTDI/T2C1ETR/SPI3_NSS_38") (pintype "passive"))
    )
    (net (code "27") (name "/PA9") (class "Default")
      (node (ref "R27") (pin "1") (pinfunction "1_1") (pintype "passive"))
      (node (ref "S19") (pin "1") (pinfunction "1_1") (pintype "passive"))
      (node (ref "S19") (pin "4") (pinfunction "4_4") (pintype "passive"))
      (node (ref "U2") (pin "45") (pinfunction "PB8/SDIO_D4/I2C1_SCL/T4C3(7)/CAN_Rx_45") (pintype "passive"))
    )
    (net (code "28") (name "/PA10") (class "Default")
      (node (ref "R30") (pin "1") (pinfunction "1_1") (pintype "passive"))
      (node (ref "S18") (pin "1") (pinfunction "1_1") (pintype "passive"))
      (node (ref "S18") (pin "4") (pinfunction "4_4") (pintype "passive"))
      (node (ref "U2") (pin "46") (pinfunction "PB9/SDIO_D5/I2C1_SDA/T4C4/CAN_Tx_46") (pintype "passive"))
    )
    (net (code "29") (name "/PA11") (class "Default")
      (node (ref "R31") (pin "1") (pinfunction "1_1") (pintype "passive"))
      (node (ref "S17") (pin "1") (pinfunction "1_1") (pintype "passive"))
      (node (ref "S17") (pin "4") (pinfunction "4_4") (pintype "passive"))
      (node (ref "U2") (pin "31") (pinfunction "PA10/T1C3/USART1_Rx_31") (pintype "passive"))
    )
    (net (code "30") (name "/PWR") (class "Default")
      (node (ref "R6") (pin "1") (pinfunction "1_1") (pintype "passive"))
      (node (ref "U2") (pin "27") (pinfunction "PB14/T1CH2N/SPI2_MISO_27") (pintype "passive"))
    )
    (net (code "31") (name "/STM_RXD3") (class "Default")
      (node (ref "R33") (pin "1") (pinfunction "1_1") (pintype "passive"))
      (node (ref "RX2") (pin "2") (pinfunction "2_2") (pintype "passive"))
      (node (ref "U2") (pin "22") (pinfunction "PB11/USART3_Rx/I2C2_SDA/T2C4_22") (pintype "passive"))
      (node (ref "U4") (pin "1") (pinfunction "R_1") (pintype "passive"))
    )
    (net (code "32") (name "/STM_SWC") (class "Default")
      (node (ref "CON1") (pin "2") (pinfunction "2_2") (pintype "passive"))
      (node (ref "U2") (pin "37") (pinfunction "PA14/JTCK/SWCLK_37") (pintype "passive"))
    )
    (net (code "33") (name "/STM_SWD") (class "Default")
      (node (ref "CON1") (pin "3") (pinfunction "3_3") (pintype "passive"))
      (node (ref "U2") (pin "34") (pinfunction "PA13/JTMS/SWDIO_34") (pintype "passive"))
    )
    (net (code "34") (name "/STM_TXD3") (class "Default")
      (node (ref "R32") (pin "1") (pinfunction "1_1") (pintype "passive"))
      (node (ref "TX1") (pin "2") (pinfunction "2_2") (pintype "passive"))
      (node (ref "U2") (pin "21") (pinfunction "PB10/USART3_Tx/I2C2_SCL/T2C3_21") (pintype "passive"))
      (node (ref "U4") (pin "4") (pinfunction "D_4") (pintype "passive"))
    )
    (net (code "35") (name "/U_SCL") (class "Default")
      (node (ref "R28") (pin "2") (pinfunction "2_2") (pintype "passive"))
      (node (ref "U2") (pin "30") (pinfunction "PA9/T1C2/USART1_Tx_30") (pintype "passive"))
      (node (ref "U3") (pin "6") (pinfunction "SCL_6") (pintype "passive"))
    )
    (net (code "36") (name "/U_SDA") (class "Default")
      (node (ref "R29") (pin "2") (pinfunction "2_2") (pintype "passive"))
      (node (ref "U2") (pin "29") (pinfunction "PA8/T1C1/MCO_29") (pintype "passive"))
      (node (ref "U3") (pin "5") (pinfunction "SDA_5") (pintype "passive"))
    )
    (net (code "37") (name "EGND") (class "Default")
      (node (ref "EC1") (pin "1") (pinfunction "1_1") (pintype "passive"))
      (node (ref "EC2") (pin "1") (pinfunction "1_1") (pintype "passive"))
      (node (ref "EC3") (pin "1") (pinfunction "1_1") (pintype "passive"))
      (node (ref "EC4") (pin "1") (pinfunction "1_1") (pintype "passive"))
      (node (ref "EGND1") (pin "0") (pinfunction "0_0") (pintype "passive"))
      (node (ref "EGND2") (pin "0") (pinfunction "0_0") (pintype "passive"))
      (node (ref "EGND3") (pin "0") (pinfunction "0_0") (pintype "passive"))
      (node (ref "EGND4") (pin "0") (pinfunction "0_0") (pintype "passive"))
      (node (ref "ER1") (pin "1") (pinfunction "1_1") (pintype "passive"))
      (node (ref "ER2") (pin "1") (pinfunction "1_1") (pintype "passive"))
      (node (ref "ER3") (pin "1") (pinfunction "1_1") (pintype "passive"))
      (node (ref "ER4") (pin "1") (pinfunction "1_1") (pintype "passive"))
      (node (ref "J2") (pin "5") (pinfunction "SHELL_5") (pintype "passive"))
      (node (ref "J2") (pin "6") (pinfunction "SHELL_6") (pintype "passive"))
    )
    (net (code "38") (name "GND") (class "Default")
      (node (ref "C1") (pin "1") (pinfunction "1_1") (pintype "passive"))
      (node (ref "C10") (pin "1") (pinfunction "1_1") (pintype "passive"))
      (node (ref "C14") (pin "2") (pinfunction "2_2") (pintype "passive"))
      (node (ref "C15") (pin "2") (pinfunction "2_2") (pintype "passive"))
      (node (ref "C27") (pin "2") (pinfunction "2_2") (pintype "passive"))
      (node (ref "C28") (pin "2") (pinfunction "2_2") (pintype "passive"))
      (node (ref "C9") (pin "1") (pinfunction "1_1") (pintype "passive"))
      (node (ref "CN1") (pin "3") (pinfunction "GND_3") (pintype "passive"))
      (node (ref "D1") (pin "1") (pinfunction "A_1") (pintype "passive"))
      (node (ref "D11") (pin "1") (pinfunction "A_1") (pintype "passive"))
      (node (ref "D17") (pin "1") (pinfunction "A_1") (pintype "passive"))
      (node (ref "D18") (pin "1") (pinfunction "A_1") (pintype "passive"))
      (node (ref "D8") (pin "1") (pinfunction "A_1") (pintype "passive"))
      (node (ref "E2") (pin "2") (pinfunction "2_2") (pintype "passive"))
      (node (ref "E6") (pin "2") (pinfunction "2_2") (pintype "passive"))
      (node (ref "E7") (pin "2") (pinfunction "2_2") (pintype "passive"))
      (node (ref "E8") (pin "2") (pinfunction "2_2") (pintype "passive"))
      (node (ref "EC2") (pin "2") (pinfunction "2_2") (pintype "passive"))
      (node (ref "EC4") (pin "2") (pinfunction "2_2") (pintype "passive"))
      (node (ref "ER2") (pin "2") (pinfunction "2_2") (pintype "passive"))
      (node (ref "ER4") (pin "2") (pinfunction "2_2") (pintype "passive"))
      (node (ref "GND1") (pin "1") (pinfunction "1_1") (pintype "passive"))
      (node (ref "J1") (pin "2") (pinfunction "2_2") (pintype "power_in"))
      (node (ref "J1") (pin "3") (pinfunction "3_3") (pintype "power_in"))
      (node (ref "J2") (pin "4") (pinfunction "VSS_4") (pintype "passive"))
      (node (ref "L2") (pin "1") (pinfunction "1_1") (pintype "passive"))
      (node (ref "R39") (pin "1") (pinfunction "1_1") (pintype "passive"))
      (node (ref "R41") (pin "2") (pinfunction "2_2") (pintype "passive"))
      (node (ref "R9") (pin "2") (pinfunction "2_2") (pintype "passive"))
      (node (ref "RISET1") (pin "2") (pinfunction "2_2") (pintype "passive"))
      (node (ref "U1") (pin "1") (pinfunction "GND_1") (pintype "passive"))
      (node (ref "U4") (pin "5") (pinfunction "GND_5") (pintype "passive"))
    )
    (net (code "39") (name "Net-(C8-Pad2)") (class "Default")
      (node (ref "C8") (pin "2") (pinfunction "2_2") (pintype "passive"))
      (node (ref "E1") (pin "1") (pinfunction "1_1") (pintype "passive"))
      (node (ref "E3") (pin "1") (pinfunction "1_1") (pintype "passive"))
      (node (ref "L1") (pin "2") (pinfunction "2_2") (pintype "passive"))
      (node (ref "R3") (pin "2") (pinfunction "2_2") (pintype "passive"))
    )
    (net (code "40") (name "Net-(C12-Pad1)") (class "Default")
      (node (ref "C12") (pin "1") (pinfunction "1_1") (pintype "passive"))
      (node (ref "R9") (pin "1") (pinfunction "1_1") (pintype "passive"))
    )
    (net (code "41") (name "Net-(C16-Pad1)") (class "Default")
      (node (ref "C16") (pin "1") (pinfunction "1_1") (pintype "passive"))
      (node (ref "P1") (pin "17") (pinfunction "17_17") (pintype "passive"))
      (node (ref "R15") (pin "2") (pinfunction "2_2") (pintype "passive"))
    )
    (net (code "42") (name "Net-(CN1-DONE)") (class "Default")
      (node (ref "CN1") (pin "6") (pinfunction "DONE_6") (pintype "passive"))
      (node (ref "D12") (pin "2") (pinfunction "K_2") (pintype "passive"))
    )
    (net (code "43") (name "Net-(CN1-FB)") (class "Default")
      (node (ref "CN1") (pin "8") (pinfunction "FB_8") (pintype "passive"))
      (node (ref "Rx1") (pin "2") (pinfunction "2_2") (pintype "passive"))
    )
    (net (code "44") (name "Net-(CN1-ISET)") (class "Default")
      (node (ref "CN1") (pin "2") (pinfunction "ISET_2") (pintype "passive"))
      (node (ref "RISET1") (pin "1") (pinfunction "1_1") (pintype "passive"))
    )
    (net (code "45") (name "Net-(CN1-TEMP)") (class "Default")
      (node (ref "CN1") (pin "1") (pinfunction "TEMP_1") (pintype "passive"))
      (node (ref "R41") (pin "1") (pinfunction "1_1") (pintype "passive"))
    )
    (net (code "46") (name "Net-(CN1-VIN)") (class "Default")
      (node (ref "C15") (pin "1") (pinfunction "1_1") (pintype "passive"))
      (node (ref "CN1") (pin "4") (pinfunction "VIN_4") (pintype "passive"))
      (node (ref "D11") (pin "2") (pinfunction "K_2") (pintype "passive"))
      (node (ref "D9") (pin "2") (pinfunction "K_2") (pintype "passive"))
      (node (ref "R8") (pin "2") (pinfunction "2_2") (pintype "passive"))
    )
    (net (code "47") (name "Net-(D3-A)") (class "Default")
      (node (ref "D3") (pin "1") (pinfunction "A_1") (pintype "passive"))
      (node (ref "D4") (pin "1") (pinfunction "A_1") (pintype "passive"))
      (node (ref "Q2") (pin "3") (pinfunction "D_3") (pintype "passive"))
      (node (ref "R5") (pin "1") (pinfunction "1_1") (pintype "passive"))
    )
    (net (code "48") (name "Net-(D6-A)") (class "Default")
      (node (ref "D6") (pin "1") (pinfunction "A_1") (pintype "passive"))
      (node (ref "D9") (pin "1") (pinfunction "A_1") (pintype "passive"))
      (node (ref "F1") (pin "1") (pinfunction "1_1") (pintype "passive"))
    )
    (net (code "49") (name "Net-(D7-K)") (class "Default")
      (node (ref "D7") (pin "2") (pinfunction "K_2") (pintype "passive"))
      (node (ref "F2") (pin "1") (pinfunction "1_1") (pintype "passive"))
    )
    (net (code "50") (name "Net-(D8-K)") (class "Default")
      (node (ref "C9") (pin "2") (pinfunction "2_2") (pintype "passive"))
      (node (ref "D8") (pin "2") (pinfunction "K_2") (pintype "passive"))
      (node (ref "E7") (pin "1") (pinfunction "1_1") (pintype "passive"))
      (node (ref "F2") (pin "2") (pinfunction "2_2") (pintype "passive"))
      (node (ref "L3") (pin "1") (pinfunction "1_1") (pintype "passive"))
    )
    (net (code "51") (name "Net-(D12-A)") (class "Default")
      (node (ref "D12") (pin "1") (pinfunction "A_1") (pintype "passive"))
      (node (ref "D13") (pin "1") (pinfunction "A_1") (pintype "passive"))
      (node (ref "R8") (pin "1") (pinfunction "1_1") (pintype "passive"))
    )
    (net (code "52") (name "Net-(D14-A)") (class "Default")
      (node (ref "D14") (pin "1") (pinfunction "A_1") (pintype "passive"))
      (node (ref "R11") (pin "1") (pinfunction "1_1") (pintype "passive"))
    )
    (net (code "53") (name "Net-(D15-A)") (class "Default")
      (node (ref "D15") (pin "1") (pinfunction "A_1") (pintype "passive"))
      (node (ref "R12") (pin "1") (pinfunction "1_1") (pintype "passive"))
    )
    (net (code "54") (name "Net-(J3-1)") (class "Default")
      (node (ref "J3") (pin "2") (pinfunction "1_2") (pintype "passive"))
      (node (ref "Q3") (pin "3") (pinfunction "C_3") (pintype "passive"))
    )
    (net (code "55") (name "Net-(Q1-G)") (class "Default")
      (node (ref "Q1") (pin "1") (pinfunction "G_1") (pintype "passive"))
      (node (ref "R4") (pin "2") (pinfunction "2_2") (pintype "passive"))
      (node (ref "R5") (pin "2") (pinfunction "2_2") (pintype "passive"))
    )
    (net (code "56") (name "Net-(Q2-G)") (class "Default")
      (node (ref "Q2") (pin "1") (pinfunction "G_1") (pintype "passive"))
      (node (ref "R6") (pin "2") (pinfunction "2_2") (pintype "passive"))
      (node (ref "R7") (pin "2") (pinfunction "2_2") (pintype "passive"))
    )
    (net (code "57") (name "Net-(Q3-B)") (class "Default")
      (node (ref "Q3") (pin "1") (pinfunction "B_1") (pintype "passive"))
      (node (ref "R24") (pin "2") (pinfunction "2_2") (pintype "passive"))
      (node (ref "R25") (pin "2") (pinfunction "2_2") (pintype "passive"))
    )
    (net (code "58") (name "Net-(R10-TAP)") (class "Default")
      (node (ref "P1") (pin "3") (pinfunction "3_3") (pintype "passive"))
      (node (ref "R10") (pin "2") (pinfunction "TAP_2") (pintype "passive"))
    )
    (net (code "59") (name "Net-(R35-Pad2)") (class "Default")
      (node (ref "R35") (pin "2") (pinfunction "2_2") (pintype "passive"))
      (node (ref "RX2") (pin "1") (pinfunction "1_1") (pintype "passive"))
    )
    (net (code "60") (name "Net-(R37-Pad2)") (class "Default")
      (node (ref "R37") (pin "2") (pinfunction "2_2") (pintype "passive"))
      (node (ref "TX1") (pin "1") (pinfunction "1_1") (pintype "passive"))
    )
    (net (code "61") (name "Net-(U2-OSC_IN)") (class "Default")
      (node (ref "C17") (pin "1") (pinfunction "1_1") (pintype "passive"))
      (node (ref "R21") (pin "2") (pinfunction "2_2") (pintype "passive"))
      (node (ref "U2") (pin "5") (pinfunction "OSC_IN_5") (pintype "passive"))
      (node (ref "Y1") (pin "1") (pinfunction "OSC1_1") (pintype "passive"))
    )
    (net (code "62") (name "Net-(U2-OSC_OUT)") (class "Default")
      (node (ref "C18") (pin "1") (pinfunction "1_1") (pintype "passive"))
      (node (ref "R21") (pin "1") (pinfunction "1_1") (pintype "passive"))
      (node (ref "U2") (pin "6") (pinfunction "OSC_OUT_6") (pintype "passive"))
      (node (ref "Y1") (pin "2") (pinfunction "OSC2_2") (pintype "passive"))
    )
    (net (code "63") (name "Net-(U4-A)") (class "Default")
      (node (ref "R34") (pin "1") (pinfunction "1_1") (pintype "passive"))
      (node (ref "R38") (pin "2") (pinfunction "2_2") (pintype "passive"))
      (node (ref "R40") (pin "1") (pinfunction "1_1") (pintype "passive"))
      (node (ref "U4") (pin "6") (pinfunction "A_6") (pintype "passive"))
    )
    (net (code "64") (name "Net-(U4-B)") (class "Default")
      (node (ref "R36") (pin "2") (pinfunction "2_2") (pintype "passive"))
      (node (ref "R39") (pin "2") (pinfunction "2_2") (pintype "passive"))
      (node (ref "R40") (pin "2") (pinfunction "2_2") (pintype "passive"))
      (node (ref "U4") (pin "7") (pinfunction "B_7") (pintype "passive"))
    )
    (net (code "65") (name "VCC-3.3V") (class "Default")
      (node (ref "C1") (pin "2") (pinfunction "2_2") (pintype "passive"))
      (node (ref "D1") (pin "2") (pinfunction "K_2") (pintype "passive"))
      (node (ref "E2") (pin "1") (pinfunction "1_1") (pintype "passive"))
      (node (ref "L1") (pin "1") (pinfunction "1_1") (pintype "passive"))
      (node (ref "U1") (pin "2") (pinfunction "OUT_2") (pintype "passive"))
    )
    (net (code "66") (name "VCC-5V") (class "Default")
      (node (ref "C10") (pin "2") (pinfunction "2_2") (pintype "passive"))
      (node (ref "C27") (pin "1") (pinfunction "1_1") (pintype "passive"))
      (node (ref "C28") (pin "1") (pinfunction "1_1") (pintype "passive"))
      (node (ref "D10") (pin "2") (pinfunction "K_2") (pintype "passive"))
      (node (ref "D6") (pin "2") (pinfunction "K_2") (pintype "passive"))
      (node (ref "E6") (pin "1") (pinfunction "1_1") (pintype "passive"))
      (node (ref "E8") (pin "1") (pinfunction "1_1") (pintype "passive"))
      (node (ref "L3") (pin "2") (pinfunction "2_2") (pintype "passive"))
      (node (ref "Q1") (pin "3") (pinfunction "D_3") (pintype "passive"))
      (node (ref "R1") (pin "1") (pinfunction "1_1") (pintype "passive"))
      (node (ref "R32") (pin "2") (pinfunction "2_2") (pintype "passive"))
      (node (ref "R33") (pin "2") (pinfunction "2_2") (pintype "passive"))
      (node (ref "R34") (pin "2") (pinfunction "2_2") (pintype "passive"))
      (node (ref "U1") (pin "3") (pinfunction "IN_3") (pintype "passive"))
      (node (ref "U4") (pin "8") (pinfunction "VCC_8") (pintype "passive"))
      (node (ref "VCC-1") (pin "1") (pinfunction "1_1") (pintype "passive"))
    )
    (net (code "67") (name "VDD") (class "Default")
      (node (ref "C2") (pin "1") (pinfunction "1_1") (pintype "passive"))
      (node (ref "C20") (pin "2") (pinfunction "2_2") (pintype "passive"))
      (node (ref "C21") (pin "2") (pinfunction "2_2") (pintype "passive"))
      (node (ref "C22") (pin "2") (pinfunction "2_2") (pintype "passive"))
      (node (ref "C23") (pin "2") (pinfunction "2_2") (pintype "passive"))
      (node (ref "C24") (pin "2") (pinfunction "2_2") (pintype "passive"))
      (node (ref "C25") (pin "2") (pinfunction "2_2") (pintype "passive"))
      (node (ref "C26") (pin "2") (pinfunction "2_2") (pintype "passive"))
      (node (ref "C3") (pin "2") (pinfunction "2_2") (pintype "passive"))
      (node (ref "C4") (pin "2") (pinfunction "2_2") (pintype "passive"))
      (node (ref "C5") (pin "2") (pinfunction "2_2") (pintype "passive"))
      (node (ref "C6") (pin "2") (pinfunction "2_2") (pintype "passive"))
      (node (ref "C7") (pin "2") (pinfunction "2_2") (pintype "passive"))
      (node (ref "CON1") (pin "4") (pinfunction "4_4") (pintype "passive"))
      (node (ref "E4") (pin "1") (pinfunction "1_1") (pintype "passive"))
      (node (ref "E5") (pin "1") (pinfunction "1_1") (pintype "passive"))
      (node (ref "J3") (pin "1") (pinfunction "0_1") (pintype "passive"))
      (node (ref "R11") (pin "2") (pinfunction "2_2") (pintype "passive"))
      (node (ref "R12") (pin "2") (pinfunction "2_2") (pintype "passive"))
      (node (ref "R13") (pin "1") (pinfunction "1_1") (pintype "passive"))
      (node (ref "R16") (pin "2") (pinfunction "2_2") (pintype "passive"))
      (node (ref "R17") (pin "2") (pinfunction "2_2") (pintype "passive"))
      (node (ref "R18") (pin "2") (pinfunction "2_2") (pintype "passive"))
      (node (ref "R20") (pin "2") (pinfunction "2_2") (pintype "passive"))
      (node (ref "R23") (pin "2") (pinfunction "2_2") (pintype "passive"))
      (node (ref "R26") (pin "2") (pinfunction "2_2") (pintype "passive"))
      (node (ref "R27") (pin "2") (pinfunction "2_2") (pintype "passive"))
      (node (ref "R28") (pin "1") (pinfunction "1_1") (pintype "passive"))
      (node (ref "R29") (pin "1") (pinfunction "1_1") (pintype "passive"))
      (node (ref "R3") (pin "1") (pinfunction "1_1") (pintype "passive"))
      (node (ref "R30") (pin "2") (pinfunction "2_2") (pintype "passive"))
      (node (ref "R31") (pin "2") (pinfunction "2_2") (pintype "passive"))
      (node (ref "R35") (pin "1") (pinfunction "1_1") (pintype "passive"))
      (node (ref "R37") (pin "1") (pinfunction "1_1") (pintype "passive"))
      (node (ref "U2") (pin "1") (pinfunction "VBAT_1") (pintype "passive"))
      (node (ref "U2") (pin "24") (pinfunction "VDD_1_24") (pintype "passive"))
      (node (ref "U2") (pin "36") (pinfunction "VDD_2_36") (pintype "passive"))
      (node (ref "U2") (pin "48") (pinfunction "VDD_3_48") (pintype "passive"))
      (node (ref "U2") (pin "9") (pinfunction "VDDA_9") (pintype "passive"))
      (node (ref "U3") (pin "8") (pinfunction "VCC_8") (pintype "passive"))
      (node (ref "VDD1") (pin "1") (pinfunction "1_1") (pintype "passive"))
    )
    (net (code "68") (name "VSS") (class "Default")
      (node (ref "C11") (pin "2") (pinfunction "2_2") (pintype "passive"))
      (node (ref "C13") (pin "2") (pinfunction "2_2") (pintype "passive"))
      (node (ref "C16") (pin "2") (pinfunction "2_2") (pintype "passive"))
      (node (ref "C17") (pin "2") (pinfunction "2_2") (pintype "passive"))
      (node (ref "C18") (pin "2") (pinfunction "2_2") (pintype "passive"))
      (node (ref "C19") (pin "1") (pinfunction "1_1") (pintype "passive"))
      (node (ref "C2") (pin "2") (pinfunction "2_2") (pintype "passive"))
      (node (ref "C20") (pin "1") (pinfunction "1_1") (pintype "passive"))
      (node (ref "C21") (pin "1") (pinfunction "1_1") (pintype "passive"))
      (node (ref "C22") (pin "1") (pinfunction "1_1") (pintype "passive"))
      (node (ref "C23") (pin "1") (pinfunction "1_1") (pintype "passive"))
      (node (ref "C24") (pin "1") (pinfunction "1_1") (pintype "passive"))
      (node (ref "C25") (pin "1") (pinfunction "1_1") (pintype "passive"))
      (node (ref "C26") (pin "1") (pinfunction "1_1") (pintype "passive"))
      (node (ref "C3") (pin "1") (pinfunction "1_1") (pintype "passive"))
      (node (ref "C4") (pin "1") (pinfunction "1_1") (pintype "passive"))
      (node (ref "C5") (pin "1") (pinfunction "1_1") (pintype "passive"))
      (node (ref "C6") (pin "1") (pinfunction "1_1") (pintype "passive"))
      (node (ref "C7") (pin "1") (pinfunction "1_1") (pintype "passive"))
      (node (ref "C8") (pin "1") (pinfunction "1_1") (pintype "passive"))
      (node (ref "CON1") (pin "1") (pinfunction "1_1") (pintype "passive"))
      (node (ref "D15") (pin "2") (pinfunction "K_2") (pintype "passive"))
      (node (ref "E1") (pin "2") (pinfunction "2_2") (pintype "passive"))
      (node (ref "E3") (pin "2") (pinfunction "2_2") (pintype "passive"))
      (node (ref "E4") (pin "2") (pinfunction "2_2") (pintype "passive"))
      (node (ref "E5") (pin "2") (pinfunction "2_2") (pintype "passive"))
      (node (ref "EC1") (pin "2") (pinfunction "2_2") (pintype "passive"))
      (node (ref "EC3") (pin "2") (pinfunction "2_2") (pintype "passive"))
      (node (ref "ER1") (pin "2") (pinfunction "2_2") (pintype "passive"))
      (node (ref "ER3") (pin "2") (pinfunction "2_2") (pintype "passive"))
      (node (ref "KEY1") (pin "2") (pinfunction "2_2") (pintype "passive"))
      (node (ref "KEY1") (pin "3") (pinfunction "3_3") (pintype "passive"))
      (node (ref "L2") (pin "2") (pinfunction "2_2") (pintype "passive"))
      (node (ref "P1") (pin "1") (pinfunction "1_1") (pintype "passive"))
      (node (ref "P1") (pin "15") (pinfunction "15_15") (pintype "passive"))
      (node (ref "P1") (pin "20") (pinfunction "20_20") (pintype "passive"))
      (node (ref "Q2") (pin "2") (pinfunction "S_2") (pintype "passive"))
      (node (ref "Q3") (pin "2") (pinfunction "E_2") (pintype "passive"))
      (node (ref "R10") (pin "1") (pinfunction "TOP_1") (pintype "passive"))
      (node (ref "R19") (pin "1") (pinfunction "1_1") (pintype "passive"))
      (node (ref "R2") (pin "2") (pinfunction "2_2") (pintype "passive"))
      (node (ref "R22") (pin "1") (pinfunction "1_1") (pintype "passive"))
      (node (ref "R25") (pin "1") (pinfunction "1_1") (pintype "passive"))
      (node (ref "R7") (pin "1") (pinfunction "1_1") (pintype "passive"))
      (node (ref "S17") (pin "2") (pinfunction "2_2") (pintype "passive"))
      (node (ref "S17") (pin "3") (pinfunction "3_3") (pintype "passive"))
      (node (ref "S18") (pin "2") (pinfunction "2_2") (pintype "passive"))
      (node (ref "S18") (pin "3") (pinfunction "3_3") (pintype "passive"))
      (node (ref "S19") (pin "2") (pinfunction "2_2") (pintype "passive"))
      (node (ref "S19") (pin "3") (pinfunction "3_3") (pintype "passive"))
      (node (ref "S20") (pin "2") (pinfunction "2_2") (pintype "passive"))
      (node (ref "S20") (pin "3") (pinfunction "3_3") (pintype "passive"))
      (node (ref "U2") (pin "23") (pinfunction "VSS_1_23") (pintype "passive"))
      (node (ref "U2") (pin "35") (pinfunction "VSS_2_35") (pintype "passive"))
      (node (ref "U2") (pin "47") (pinfunction "VSS_3_47") (pintype "passive"))
      (node (ref "U2") (pin "8") (pinfunction "VSSA_8") (pintype "passive"))
      (node (ref "U3") (pin "1") (pinfunction "A0_1") (pintype "passive"))
      (node (ref "U3") (pin "2") (pinfunction "A1_2") (pintype "passive"))
      (node (ref "U3") (pin "3") (pinfunction "A2_3") (pintype "passive"))
      (node (ref "U3") (pin "4") (pinfunction "VSS_4") (pintype "passive"))
      (node (ref "U3") (pin "7") (pinfunction "WP_7") (pintype "passive"))
      (node (ref "VSS1") (pin "1") (pinfunction "1_1") (pintype "passive"))
    )
    (net (code "69") (name "VUSB") (class "Default")
      (node (ref "D7") (pin "1") (pinfunction "A_1") (pintype "passive"))
      (node (ref "F1") (pin "2") (pinfunction "2_2") (pintype "passive"))
      (node (ref "J1") (pin "1") (pinfunction "1_1") (pintype "power_in"))
      (node (ref "J2") (pin "1") (pinfunction "VCC_1") (pintype "passive"))
      (node (ref "R14") (pin "1") (pinfunction "1_1") (pintype "passive"))
      (node (ref "VUSB1") (pin "1") (pinfunction "1_1") (pintype "passive"))
    )
    (net (code "70") (name "V_BAT") (class "Default")
      (node (ref "C12") (pin "2") (pinfunction "2_2") (pintype "passive"))
      (node (ref "C14") (pin "1") (pinfunction "1_1") (pintype "passive"))
      (node (ref "CN1") (pin "5") (pinfunction "BAT_5") (pintype "passive"))
      (node (ref "D10") (pin "1") (pinfunction "A_1") (pintype "passive"))
      (node (ref "Q1") (pin "2") (pinfunction "S_2") (pintype "passive"))
      (node (ref "R4") (pin "1") (pinfunction "1_1") (pintype "passive"))
      (node (ref "Rx1") (pin "1") (pinfunction "1_1") (pintype "passive"))
      (node (ref "V_BAT1") (pin "1") (pinfunction "1_1") (pintype "passive"))
    )
    (net (code "71") (name "unconnected-(P1-Pad7)") (class "Default")
      (node (ref "P1") (pin "7") (pinfunction "7_7") (pintype "passive"))
    )
    (net (code "72") (name "unconnected-(P1-Pad8)") (class "Default")
      (node (ref "P1") (pin "8") (pinfunction "8_8") (pintype "passive"))
    )
    (net (code "73") (name "unconnected-(P1-Pad9)") (class "Default")
      (node (ref "P1") (pin "9") (pinfunction "9_9") (pintype "passive"))
    )
    (net (code "74") (name "unconnected-(P1-Pad10)") (class "Default")
      (node (ref "P1") (pin "10") (pinfunction "10_10") (pintype "passive"))
    )
    (net (code "75") (name "unconnected-(P1-Pad11)") (class "Default")
      (node (ref "P1") (pin "11") (pinfunction "11_11") (pintype "passive"))
    )
    (net (code "76") (name "unconnected-(P1-Pad12)") (class "Default")
      (node (ref "P1") (pin "12") (pinfunction "12_12") (pintype "passive"))
    )
    (net (code "77") (name "unconnected-(P1-Pad13)") (class "Default")
      (node (ref "P1") (pin "13") (pinfunction "13_13") (pintype "passive"))
    )
    (net (code "78") (name "unconnected-(P1-Pad14)") (class "Default")
      (node (ref "P1") (pin "14") (pinfunction "14_14") (pintype "passive"))
    )
    (net (code "79") (name "unconnected-(P1-Pad16)") (class "Default")
      (node (ref "P1") (pin "16") (pinfunction "16_16") (pintype "passive"))
    )
    (net (code "80") (name "unconnected-(P1-Pad18)") (class "Default")
      (node (ref "P1") (pin "18") (pinfunction "18_18") (pintype "passive"))
    )
    (net (code "81") (name "unconnected-(U2-PB6{slash}I2C1_SCL{slash}T4C1{slash}USART1_Tx-Pad42)") (class "Default")
      (node (ref "U2") (pin "42") (pinfunction "PB6/I2C1_SCL/T4C1/USART1_Tx_42") (pintype "passive"))
    )
    (net (code "82") (name "unconnected-(U2-PB12{slash}I2S2_WS{slash}T1BKIN{slash}SPI2_NSS{slash}I2C2_SMBA-Pad25)") (class "Default")
      (node (ref "U2") (pin "25") (pinfunction "PB12/I2S2_WS/T1BKIN/SPI2_NSS/I2C2_SMBA_25") (pintype "passive"))
    )
    (net (code "83") (name "unconnected-(U2-PC13-TAMPER-RTC-Pad2)") (class "Default")
      (node (ref "U2") (pin "2") (pinfunction "PC13-TAMPER-RTC_2") (pintype "passive"))
    )
    (net (code "84") (name "unconnected-(U2-PC14-OSC32_IN-Pad3)") (class "Default")
      (node (ref "U2") (pin "3") (pinfunction "PC14-OSC32_IN_3") (pintype "passive"))
    )
    (net (code "85") (name "unconnected-(U2-PC15-OSC32_OUT-Pad4)") (class "Default")
      (node (ref "U2") (pin "4") (pinfunction "PC15-OSC32_OUT_4") (pintype "passive"))
    )
  )
)
